# angrlline6.net
KiCad netlist of a schematic drawn in EAGLE
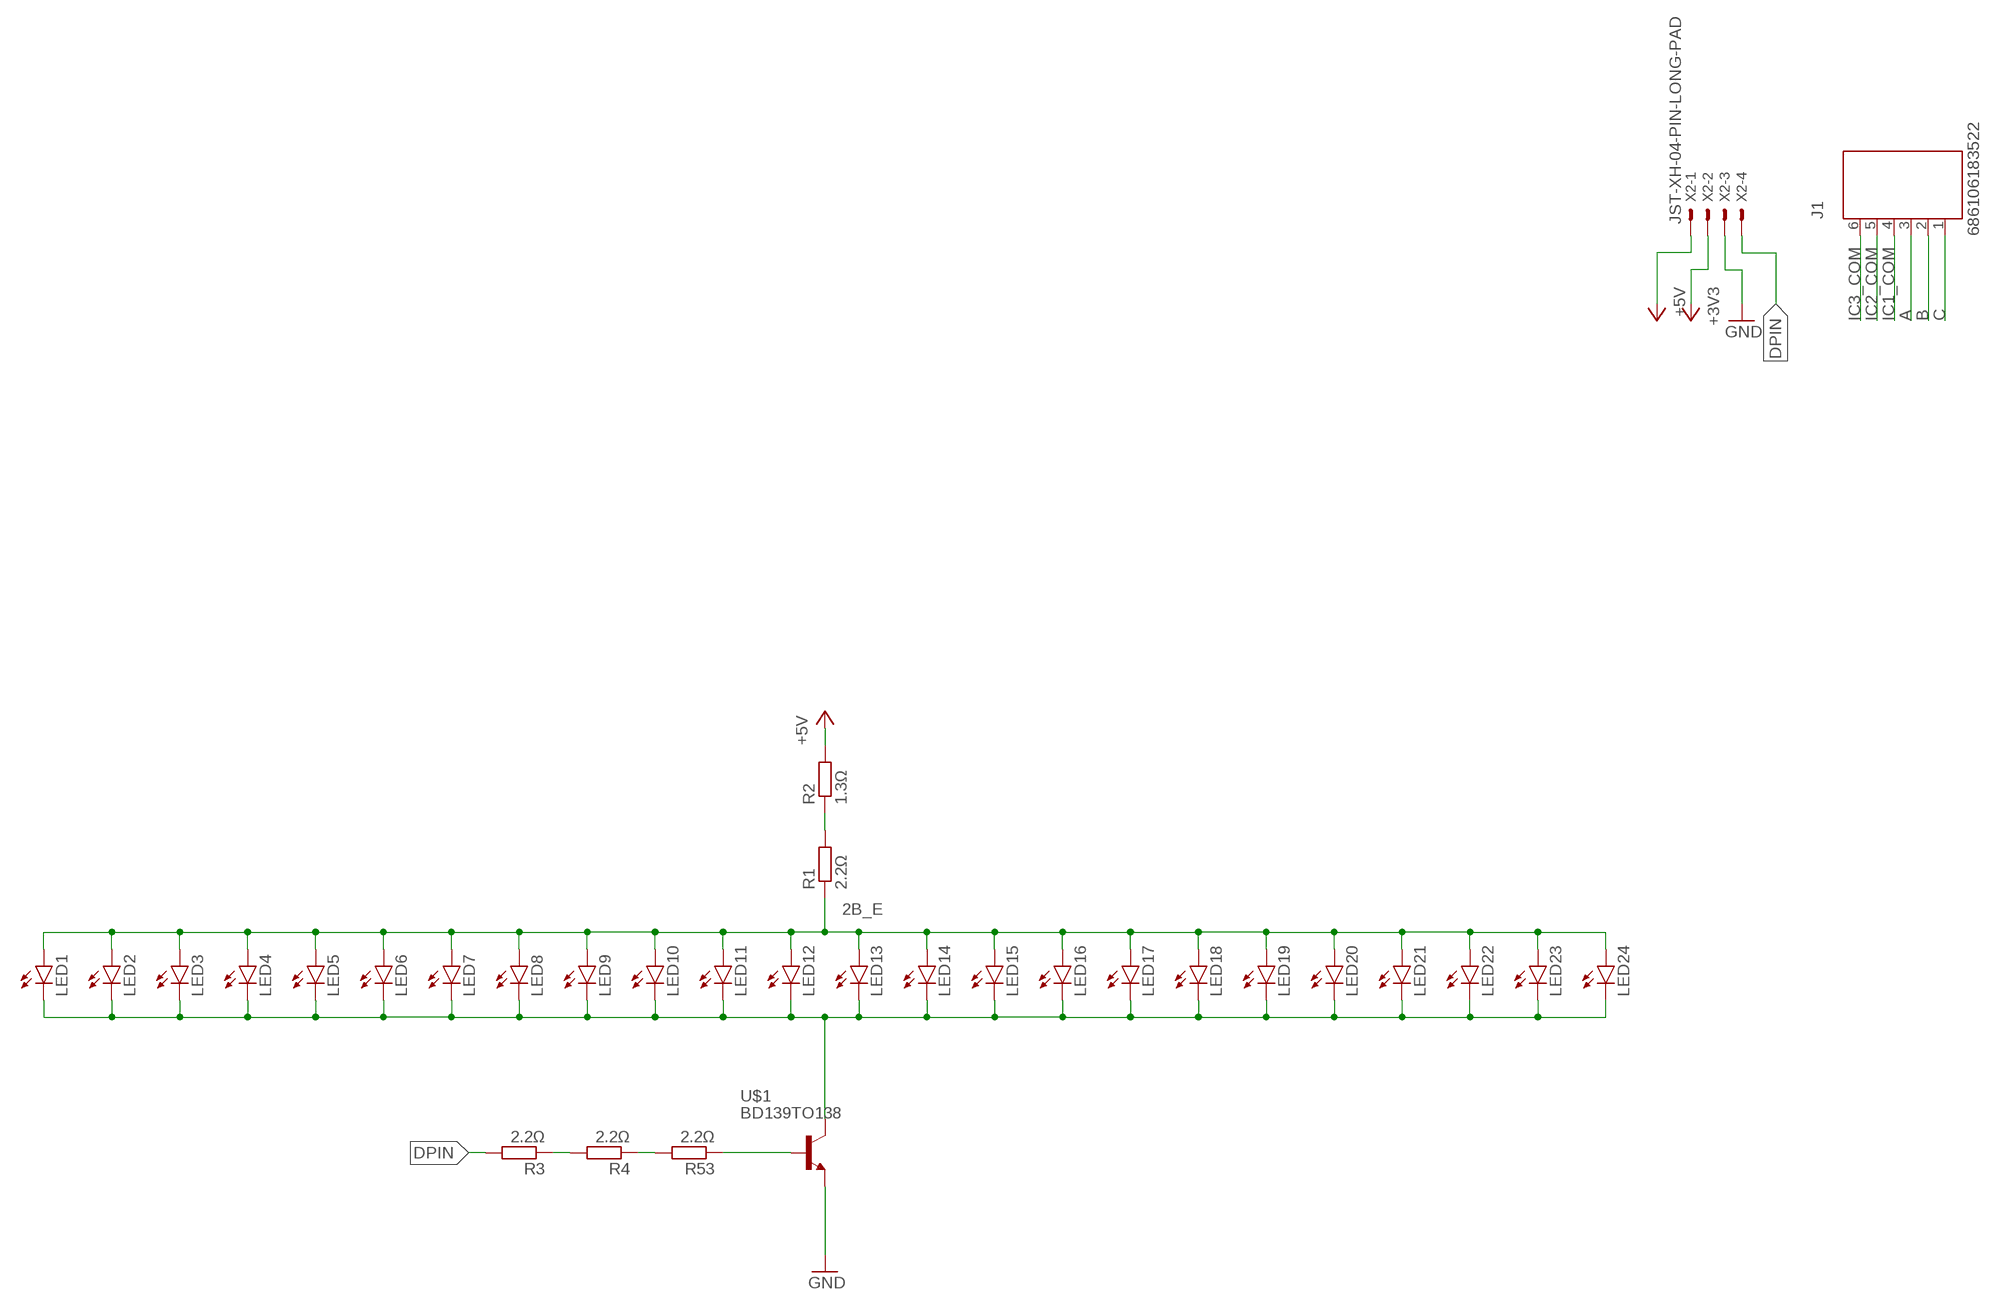
[diagram p0: schematic, sheet 1, part 1 of 2]
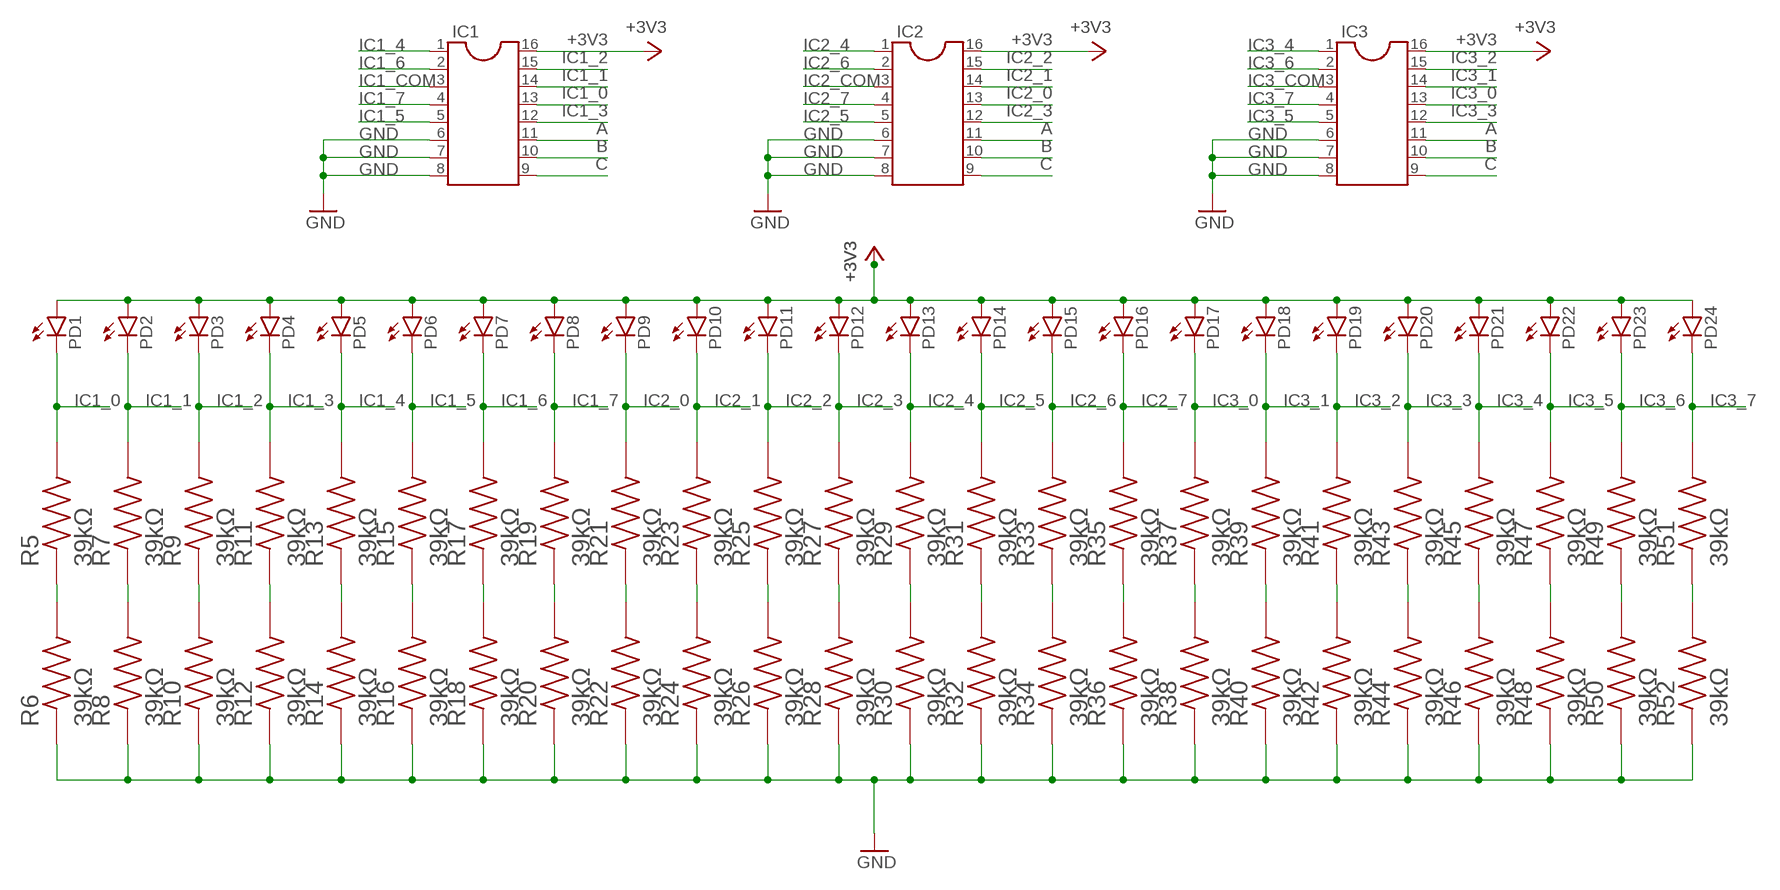
[diagram p1: schematic, sheet 1, part 2 of 2]

(export (version "E")
  (design (tool "Eeschema 10.0.6"))
  (components
    (comp (ref "IC1")
      (value "DIL16")
      (footprint "eagle-import:DIL16")
      (libsource (lib "eagle-import") (part "DIL16"))
    )
    (comp (ref "IC2")
      (value "DIL16")
      (footprint "eagle-import:DIL16")
      (libsource (lib "eagle-import") (part "DIL16"))
    )
    (comp (ref "IC3")
      (value "DIL16")
      (footprint "eagle-import:DIL16")
      (libsource (lib "eagle-import") (part "DIL16"))
    )
    (comp (ref "J1")
      (value "686106183522")
      (footprint "eagle-import:686106183522")
      (fields (field (name "MF") "Wurth Electronics"))
      (libsource (lib "eagle-import") (part "686106183522"))
    )
    (comp (ref "LED1")
      (value "LED3MM")
      (footprint "eagle-import:LED3MM")
      (libsource (lib "eagle-import") (part "LED3MM"))
    )
    (comp (ref "LED2")
      (value "LED3MM")
      (footprint "eagle-import:LED3MM")
      (libsource (lib "eagle-import") (part "LED3MM"))
    )
    (comp (ref "LED3")
      (value "LED3MM")
      (footprint "eagle-import:LED3MM")
      (libsource (lib "eagle-import") (part "LED3MM"))
    )
    (comp (ref "LED4")
      (value "LED3MM")
      (footprint "eagle-import:LED3MM")
      (libsource (lib "eagle-import") (part "LED3MM"))
    )
    (comp (ref "LED5")
      (value "LED3MM")
      (footprint "eagle-import:LED3MM")
      (libsource (lib "eagle-import") (part "LED3MM"))
    )
    (comp (ref "LED6")
      (value "LED3MM")
      (footprint "eagle-import:LED3MM")
      (libsource (lib "eagle-import") (part "LED3MM"))
    )
    (comp (ref "LED7")
      (value "LED3MM")
      (footprint "eagle-import:LED3MM")
      (libsource (lib "eagle-import") (part "LED3MM"))
    )
    (comp (ref "LED8")
      (value "LED3MM")
      (footprint "eagle-import:LED3MM")
      (libsource (lib "eagle-import") (part "LED3MM"))
    )
    (comp (ref "LED9")
      (value "LED3MM")
      (footprint "eagle-import:LED3MM")
      (libsource (lib "eagle-import") (part "LED3MM"))
    )
    (comp (ref "LED10")
      (value "LED3MM")
      (footprint "eagle-import:LED3MM")
      (libsource (lib "eagle-import") (part "LED3MM"))
    )
    (comp (ref "LED11")
      (value "LED3MM")
      (footprint "eagle-import:LED3MM")
      (libsource (lib "eagle-import") (part "LED3MM"))
    )
    (comp (ref "LED12")
      (value "LED3MM")
      (footprint "eagle-import:LED3MM")
      (libsource (lib "eagle-import") (part "LED3MM"))
    )
    (comp (ref "LED13")
      (value "LED3MM")
      (footprint "eagle-import:LED3MM")
      (libsource (lib "eagle-import") (part "LED3MM"))
    )
    (comp (ref "LED14")
      (value "LED3MM")
      (footprint "eagle-import:LED3MM")
      (libsource (lib "eagle-import") (part "LED3MM"))
    )
    (comp (ref "LED15")
      (value "LED3MM")
      (footprint "eagle-import:LED3MM")
      (libsource (lib "eagle-import") (part "LED3MM"))
    )
    (comp (ref "LED16")
      (value "LED3MM")
      (footprint "eagle-import:LED3MM")
      (libsource (lib "eagle-import") (part "LED3MM"))
    )
    (comp (ref "LED17")
      (value "LED3MM")
      (footprint "eagle-import:LED3MM")
      (libsource (lib "eagle-import") (part "LED3MM"))
    )
    (comp (ref "LED18")
      (value "LED3MM")
      (footprint "eagle-import:LED3MM")
      (libsource (lib "eagle-import") (part "LED3MM"))
    )
    (comp (ref "LED19")
      (value "LED3MM")
      (footprint "eagle-import:LED3MM")
      (libsource (lib "eagle-import") (part "LED3MM"))
    )
    (comp (ref "LED20")
      (value "LED3MM")
      (footprint "eagle-import:LED3MM")
      (libsource (lib "eagle-import") (part "LED3MM"))
    )
    (comp (ref "LED21")
      (value "LED3MM")
      (footprint "eagle-import:LED3MM")
      (libsource (lib "eagle-import") (part "LED3MM"))
    )
    (comp (ref "LED22")
      (value "LED3MM")
      (footprint "eagle-import:LED3MM")
      (libsource (lib "eagle-import") (part "LED3MM"))
    )
    (comp (ref "LED23")
      (value "LED3MM")
      (footprint "eagle-import:LED3MM")
      (libsource (lib "eagle-import") (part "LED3MM"))
    )
    (comp (ref "LED24")
      (value "LED3MM")
      (footprint "eagle-import:LED3MM")
      (libsource (lib "eagle-import") (part "LED3MM"))
    )
    (comp (ref "PD1")
      (value "LED3MM")
      (footprint "eagle-import:LED3MM")
      (libsource (lib "eagle-import") (part "LED3MM"))
    )
    (comp (ref "PD2")
      (value "LED3MM")
      (footprint "eagle-import:LED3MM")
      (libsource (lib "eagle-import") (part "LED3MM"))
    )
    (comp (ref "PD3")
      (value "LED3MM")
      (footprint "eagle-import:LED3MM")
      (libsource (lib "eagle-import") (part "LED3MM"))
    )
    (comp (ref "PD4")
      (value "LED3MM")
      (footprint "eagle-import:LED3MM")
      (libsource (lib "eagle-import") (part "LED3MM"))
    )
    (comp (ref "PD5")
      (value "LED3MM")
      (footprint "eagle-import:LED3MM")
      (libsource (lib "eagle-import") (part "LED3MM"))
    )
    (comp (ref "PD6")
      (value "LED3MM")
      (footprint "eagle-import:LED3MM")
      (libsource (lib "eagle-import") (part "LED3MM"))
    )
    (comp (ref "PD7")
      (value "LED3MM")
      (footprint "eagle-import:LED3MM")
      (libsource (lib "eagle-import") (part "LED3MM"))
    )
    (comp (ref "PD8")
      (value "LED3MM")
      (footprint "eagle-import:LED3MM")
      (libsource (lib "eagle-import") (part "LED3MM"))
    )
    (comp (ref "PD9")
      (value "LED3MM")
      (footprint "eagle-import:LED3MM")
      (libsource (lib "eagle-import") (part "LED3MM"))
    )
    (comp (ref "PD10")
      (value "LED3MM")
      (footprint "eagle-import:LED3MM")
      (libsource (lib "eagle-import") (part "LED3MM"))
    )
    (comp (ref "PD11")
      (value "LED3MM")
      (footprint "eagle-import:LED3MM")
      (libsource (lib "eagle-import") (part "LED3MM"))
    )
    (comp (ref "PD12")
      (value "LED3MM")
      (footprint "eagle-import:LED3MM")
      (libsource (lib "eagle-import") (part "LED3MM"))
    )
    (comp (ref "PD13")
      (value "LED3MM")
      (footprint "eagle-import:LED3MM")
      (libsource (lib "eagle-import") (part "LED3MM"))
    )
    (comp (ref "PD14")
      (value "LED3MM")
      (footprint "eagle-import:LED3MM")
      (libsource (lib "eagle-import") (part "LED3MM"))
    )
    (comp (ref "PD15")
      (value "LED3MM")
      (footprint "eagle-import:LED3MM")
      (libsource (lib "eagle-import") (part "LED3MM"))
    )
    (comp (ref "PD16")
      (value "LED3MM")
      (footprint "eagle-import:LED3MM")
      (libsource (lib "eagle-import") (part "LED3MM"))
    )
    (comp (ref "PD17")
      (value "LED3MM")
      (footprint "eagle-import:LED3MM")
      (libsource (lib "eagle-import") (part "LED3MM"))
    )
    (comp (ref "PD18")
      (value "LED3MM")
      (footprint "eagle-import:LED3MM")
      (libsource (lib "eagle-import") (part "LED3MM"))
    )
    (comp (ref "PD19")
      (value "LED3MM")
      (footprint "eagle-import:LED3MM")
      (libsource (lib "eagle-import") (part "LED3MM"))
    )
    (comp (ref "PD20")
      (value "LED3MM")
      (footprint "eagle-import:LED3MM")
      (libsource (lib "eagle-import") (part "LED3MM"))
    )
    (comp (ref "PD21")
      (value "LED3MM")
      (footprint "eagle-import:LED3MM")
      (libsource (lib "eagle-import") (part "LED3MM"))
    )
    (comp (ref "PD22")
      (value "LED3MM")
      (footprint "eagle-import:LED3MM")
      (libsource (lib "eagle-import") (part "LED3MM"))
    )
    (comp (ref "PD23")
      (value "LED3MM")
      (footprint "eagle-import:LED3MM")
      (libsource (lib "eagle-import") (part "LED3MM"))
    )
    (comp (ref "PD24")
      (value "LED3MM")
      (footprint "eagle-import:LED3MM")
      (libsource (lib "eagle-import") (part "LED3MM"))
    )
    (comp (ref "R1")
      (value "2.2Ω")
      (footprint "eagle-import:0207_10")
      (libsource (lib "eagle-import") (part "R-EU_0207/10"))
    )
    (comp (ref "R2")
      (value "1.3Ω")
      (footprint "eagle-import:0207_10")
      (libsource (lib "eagle-import") (part "R-EU_0207/10"))
    )
    (comp (ref "R3")
      (value "2.2Ω")
      (footprint "eagle-import:0207_10")
      (libsource (lib "eagle-import") (part "R-EU_0207/10"))
    )
    (comp (ref "R4")
      (value "2.2Ω")
      (footprint "eagle-import:0207_10")
      (libsource (lib "eagle-import") (part "R-EU_0207/10"))
    )
    (comp (ref "R5")
      (value "39kΩ")
      (footprint "eagle-import:RESC1608X55N")
      (fields
        (field (name "COMMENT") "1623094-1")
        (field (name "MF") "TE Connectivity")
        (field (name "MP") "CRG0603ZR")
      )
      (libsource (lib "eagle-import") (part "CRG0603ZR"))
    )
    (comp (ref "R6")
      (value "39kΩ")
      (footprint "eagle-import:RESC1608X55N")
      (fields
        (field (name "COMMENT") "1623094-1")
        (field (name "MF") "TE Connectivity")
        (field (name "MP") "CRG0603ZR")
      )
      (libsource (lib "eagle-import") (part "CRG0603ZR"))
    )
    (comp (ref "R7")
      (value "39kΩ")
      (footprint "eagle-import:RESC1608X55N")
      (fields
        (field (name "COMMENT") "1623094-1")
        (field (name "MF") "TE Connectivity")
        (field (name "MP") "CRG0603ZR")
      )
      (libsource (lib "eagle-import") (part "CRG0603ZR"))
    )
    (comp (ref "R8")
      (value "39kΩ")
      (footprint "eagle-import:RESC1608X55N")
      (fields
        (field (name "COMMENT") "1623094-1")
        (field (name "MF") "TE Connectivity")
        (field (name "MP") "CRG0603ZR")
      )
      (libsource (lib "eagle-import") (part "CRG0603ZR"))
    )
    (comp (ref "R9")
      (value "39kΩ")
      (footprint "eagle-import:RESC1608X55N")
      (fields
        (field (name "COMMENT") "1623094-1")
        (field (name "MF") "TE Connectivity")
        (field (name "MP") "CRG0603ZR")
      )
      (libsource (lib "eagle-import") (part "CRG0603ZR"))
    )
    (comp (ref "R10")
      (value "39kΩ")
      (footprint "eagle-import:RESC1608X55N")
      (fields
        (field (name "COMMENT") "1623094-1")
        (field (name "MF") "TE Connectivity")
        (field (name "MP") "CRG0603ZR")
      )
      (libsource (lib "eagle-import") (part "CRG0603ZR"))
    )
    (comp (ref "R11")
      (value "39kΩ")
      (footprint "eagle-import:RESC1608X55N")
      (fields
        (field (name "COMMENT") "1623094-1")
        (field (name "MF") "TE Connectivity")
        (field (name "MP") "CRG0603ZR")
      )
      (libsource (lib "eagle-import") (part "CRG0603ZR"))
    )
    (comp (ref "R12")
      (value "39kΩ")
      (footprint "eagle-import:RESC1608X55N")
      (fields
        (field (name "COMMENT") "1623094-1")
        (field (name "MF") "TE Connectivity")
        (field (name "MP") "CRG0603ZR")
      )
      (libsource (lib "eagle-import") (part "CRG0603ZR"))
    )
    (comp (ref "R13")
      (value "39kΩ")
      (footprint "eagle-import:RESC1608X55N")
      (fields
        (field (name "COMMENT") "1623094-1")
        (field (name "MF") "TE Connectivity")
        (field (name "MP") "CRG0603ZR")
      )
      (libsource (lib "eagle-import") (part "CRG0603ZR"))
    )
    (comp (ref "R14")
      (value "39kΩ")
      (footprint "eagle-import:RESC1608X55N")
      (fields
        (field (name "COMMENT") "1623094-1")
        (field (name "MF") "TE Connectivity")
        (field (name "MP") "CRG0603ZR")
      )
      (libsource (lib "eagle-import") (part "CRG0603ZR"))
    )
    (comp (ref "R15")
      (value "39kΩ")
      (footprint "eagle-import:RESC1608X55N")
      (fields
        (field (name "COMMENT") "1623094-1")
        (field (name "MF") "TE Connectivity")
        (field (name "MP") "CRG0603ZR")
      )
      (libsource (lib "eagle-import") (part "CRG0603ZR"))
    )
    (comp (ref "R16")
      (value "39kΩ")
      (footprint "eagle-import:RESC1608X55N")
      (fields
        (field (name "COMMENT") "1623094-1")
        (field (name "MF") "TE Connectivity")
        (field (name "MP") "CRG0603ZR")
      )
      (libsource (lib "eagle-import") (part "CRG0603ZR"))
    )
    (comp (ref "R17")
      (value "39kΩ")
      (footprint "eagle-import:RESC1608X55N")
      (fields
        (field (name "COMMENT") "1623094-1")
        (field (name "MF") "TE Connectivity")
        (field (name "MP") "CRG0603ZR")
      )
      (libsource (lib "eagle-import") (part "CRG0603ZR"))
    )
    (comp (ref "R18")
      (value "39kΩ")
      (footprint "eagle-import:RESC1608X55N")
      (fields
        (field (name "COMMENT") "1623094-1")
        (field (name "MF") "TE Connectivity")
        (field (name "MP") "CRG0603ZR")
      )
      (libsource (lib "eagle-import") (part "CRG0603ZR"))
    )
    (comp (ref "R19")
      (value "39kΩ")
      (footprint "eagle-import:RESC1608X55N")
      (fields
        (field (name "COMMENT") "1623094-1")
        (field (name "MF") "TE Connectivity")
        (field (name "MP") "CRG0603ZR")
      )
      (libsource (lib "eagle-import") (part "CRG0603ZR"))
    )
    (comp (ref "R20")
      (value "39kΩ")
      (footprint "eagle-import:RESC1608X55N")
      (fields
        (field (name "COMMENT") "1623094-1")
        (field (name "MF") "TE Connectivity")
        (field (name "MP") "CRG0603ZR")
      )
      (libsource (lib "eagle-import") (part "CRG0603ZR"))
    )
    (comp (ref "R21")
      (value "39kΩ")
      (footprint "eagle-import:RESC1608X55N")
      (fields
        (field (name "COMMENT") "1623094-1")
        (field (name "MF") "TE Connectivity")
        (field (name "MP") "CRG0603ZR")
      )
      (libsource (lib "eagle-import") (part "CRG0603ZR"))
    )
    (comp (ref "R22")
      (value "39kΩ")
      (footprint "eagle-import:RESC1608X55N")
      (fields
        (field (name "COMMENT") "1623094-1")
        (field (name "MF") "TE Connectivity")
        (field (name "MP") "CRG0603ZR")
      )
      (libsource (lib "eagle-import") (part "CRG0603ZR"))
    )
    (comp (ref "R23")
      (value "39kΩ")
      (footprint "eagle-import:RESC1608X55N")
      (fields
        (field (name "COMMENT") "1623094-1")
        (field (name "MF") "TE Connectivity")
        (field (name "MP") "CRG0603ZR")
      )
      (libsource (lib "eagle-import") (part "CRG0603ZR"))
    )
    (comp (ref "R24")
      (value "39kΩ")
      (footprint "eagle-import:RESC1608X55N")
      (fields
        (field (name "COMMENT") "1623094-1")
        (field (name "MF") "TE Connectivity")
        (field (name "MP") "CRG0603ZR")
      )
      (libsource (lib "eagle-import") (part "CRG0603ZR"))
    )
    (comp (ref "R25")
      (value "39kΩ")
      (footprint "eagle-import:RESC1608X55N")
      (fields
        (field (name "COMMENT") "1623094-1")
        (field (name "MF") "TE Connectivity")
        (field (name "MP") "CRG0603ZR")
      )
      (libsource (lib "eagle-import") (part "CRG0603ZR"))
    )
    (comp (ref "R26")
      (value "39kΩ")
      (footprint "eagle-import:RESC1608X55N")
      (fields
        (field (name "COMMENT") "1623094-1")
        (field (name "MF") "TE Connectivity")
        (field (name "MP") "CRG0603ZR")
      )
      (libsource (lib "eagle-import") (part "CRG0603ZR"))
    )
    (comp (ref "R27")
      (value "39kΩ")
      (footprint "eagle-import:RESC1608X55N")
      (fields
        (field (name "COMMENT") "1623094-1")
        (field (name "MF") "TE Connectivity")
        (field (name "MP") "CRG0603ZR")
      )
      (libsource (lib "eagle-import") (part "CRG0603ZR"))
    )
    (comp (ref "R28")
      (value "39kΩ")
      (footprint "eagle-import:RESC1608X55N")
      (fields
        (field (name "COMMENT") "1623094-1")
        (field (name "MF") "TE Connectivity")
        (field (name "MP") "CRG0603ZR")
      )
      (libsource (lib "eagle-import") (part "CRG0603ZR"))
    )
    (comp (ref "R29")
      (value "39kΩ")
      (footprint "eagle-import:RESC1608X55N")
      (fields
        (field (name "COMMENT") "1623094-1")
        (field (name "MF") "TE Connectivity")
        (field (name "MP") "CRG0603ZR")
      )
      (libsource (lib "eagle-import") (part "CRG0603ZR"))
    )
    (comp (ref "R30")
      (value "39kΩ")
      (footprint "eagle-import:RESC1608X55N")
      (fields
        (field (name "COMMENT") "1623094-1")
        (field (name "MF") "TE Connectivity")
        (field (name "MP") "CRG0603ZR")
      )
      (libsource (lib "eagle-import") (part "CRG0603ZR"))
    )
    (comp (ref "R31")
      (value "39kΩ")
      (footprint "eagle-import:RESC1608X55N")
      (fields
        (field (name "COMMENT") "1623094-1")
        (field (name "MF") "TE Connectivity")
        (field (name "MP") "CRG0603ZR")
      )
      (libsource (lib "eagle-import") (part "CRG0603ZR"))
    )
    (comp (ref "R32")
      (value "39kΩ")
      (footprint "eagle-import:RESC1608X55N")
      (fields
        (field (name "COMMENT") "1623094-1")
        (field (name "MF") "TE Connectivity")
        (field (name "MP") "CRG0603ZR")
      )
      (libsource (lib "eagle-import") (part "CRG0603ZR"))
    )
    (comp (ref "R33")
      (value "39kΩ")
      (footprint "eagle-import:RESC1608X55N")
      (fields
        (field (name "COMMENT") "1623094-1")
        (field (name "MF") "TE Connectivity")
        (field (name "MP") "CRG0603ZR")
      )
      (libsource (lib "eagle-import") (part "CRG0603ZR"))
    )
    (comp (ref "R34")
      (value "39kΩ")
      (footprint "eagle-import:RESC1608X55N")
      (fields
        (field (name "COMMENT") "1623094-1")
        (field (name "MF") "TE Connectivity")
        (field (name "MP") "CRG0603ZR")
      )
      (libsource (lib "eagle-import") (part "CRG0603ZR"))
    )
    (comp (ref "R35")
      (value "39kΩ")
      (footprint "eagle-import:RESC1608X55N")
      (fields
        (field (name "COMMENT") "1623094-1")
        (field (name "MF") "TE Connectivity")
        (field (name "MP") "CRG0603ZR")
      )
      (libsource (lib "eagle-import") (part "CRG0603ZR"))
    )
    (comp (ref "R36")
      (value "39kΩ")
      (footprint "eagle-import:RESC1608X55N")
      (fields
        (field (name "COMMENT") "1623094-1")
        (field (name "MF") "TE Connectivity")
        (field (name "MP") "CRG0603ZR")
      )
      (libsource (lib "eagle-import") (part "CRG0603ZR"))
    )
    (comp (ref "R37")
      (value "39kΩ")
      (footprint "eagle-import:RESC1608X55N")
      (fields
        (field (name "COMMENT") "1623094-1")
        (field (name "MF") "TE Connectivity")
        (field (name "MP") "CRG0603ZR")
      )
      (libsource (lib "eagle-import") (part "CRG0603ZR"))
    )
    (comp (ref "R38")
      (value "39kΩ")
      (footprint "eagle-import:RESC1608X55N")
      (fields
        (field (name "COMMENT") "1623094-1")
        (field (name "MF") "TE Connectivity")
        (field (name "MP") "CRG0603ZR")
      )
      (libsource (lib "eagle-import") (part "CRG0603ZR"))
    )
    (comp (ref "R39")
      (value "39kΩ")
      (footprint "eagle-import:RESC1608X55N")
      (fields
        (field (name "COMMENT") "1623094-1")
        (field (name "MF") "TE Connectivity")
        (field (name "MP") "CRG0603ZR")
      )
      (libsource (lib "eagle-import") (part "CRG0603ZR"))
    )
    (comp (ref "R40")
      (value "39kΩ")
      (footprint "eagle-import:RESC1608X55N")
      (fields
        (field (name "COMMENT") "1623094-1")
        (field (name "MF") "TE Connectivity")
        (field (name "MP") "CRG0603ZR")
      )
      (libsource (lib "eagle-import") (part "CRG0603ZR"))
    )
    (comp (ref "R41")
      (value "39kΩ")
      (footprint "eagle-import:RESC1608X55N")
      (fields
        (field (name "COMMENT") "1623094-1")
        (field (name "MF") "TE Connectivity")
        (field (name "MP") "CRG0603ZR")
      )
      (libsource (lib "eagle-import") (part "CRG0603ZR"))
    )
    (comp (ref "R42")
      (value "39kΩ")
      (footprint "eagle-import:RESC1608X55N")
      (fields
        (field (name "COMMENT") "1623094-1")
        (field (name "MF") "TE Connectivity")
        (field (name "MP") "CRG0603ZR")
      )
      (libsource (lib "eagle-import") (part "CRG0603ZR"))
    )
    (comp (ref "R43")
      (value "39kΩ")
      (footprint "eagle-import:RESC1608X55N")
      (fields
        (field (name "COMMENT") "1623094-1")
        (field (name "MF") "TE Connectivity")
        (field (name "MP") "CRG0603ZR")
      )
      (libsource (lib "eagle-import") (part "CRG0603ZR"))
    )
    (comp (ref "R44")
      (value "39kΩ")
      (footprint "eagle-import:RESC1608X55N")
      (fields
        (field (name "COMMENT") "1623094-1")
        (field (name "MF") "TE Connectivity")
        (field (name "MP") "CRG0603ZR")
      )
      (libsource (lib "eagle-import") (part "CRG0603ZR"))
    )
    (comp (ref "R45")
      (value "39kΩ")
      (footprint "eagle-import:RESC1608X55N")
      (fields
        (field (name "COMMENT") "1623094-1")
        (field (name "MF") "TE Connectivity")
        (field (name "MP") "CRG0603ZR")
      )
      (libsource (lib "eagle-import") (part "CRG0603ZR"))
    )
    (comp (ref "R46")
      (value "39kΩ")
      (footprint "eagle-import:RESC1608X55N")
      (fields
        (field (name "COMMENT") "1623094-1")
        (field (name "MF") "TE Connectivity")
        (field (name "MP") "CRG0603ZR")
      )
      (libsource (lib "eagle-import") (part "CRG0603ZR"))
    )
    (comp (ref "R47")
      (value "39kΩ")
      (footprint "eagle-import:RESC1608X55N")
      (fields
        (field (name "COMMENT") "1623094-1")
        (field (name "MF") "TE Connectivity")
        (field (name "MP") "CRG0603ZR")
      )
      (libsource (lib "eagle-import") (part "CRG0603ZR"))
    )
    (comp (ref "R48")
      (value "39kΩ")
      (footprint "eagle-import:RESC1608X55N")
      (fields
        (field (name "COMMENT") "1623094-1")
        (field (name "MF") "TE Connectivity")
        (field (name "MP") "CRG0603ZR")
      )
      (libsource (lib "eagle-import") (part "CRG0603ZR"))
    )
    (comp (ref "R49")
      (value "39kΩ")
      (footprint "eagle-import:RESC1608X55N")
      (fields
        (field (name "COMMENT") "1623094-1")
        (field (name "MF") "TE Connectivity")
        (field (name "MP") "CRG0603ZR")
      )
      (libsource (lib "eagle-import") (part "CRG0603ZR"))
    )
    (comp (ref "R50")
      (value "39kΩ")
      (footprint "eagle-import:RESC1608X55N")
      (fields
        (field (name "COMMENT") "1623094-1")
        (field (name "MF") "TE Connectivity")
        (field (name "MP") "CRG0603ZR")
      )
      (libsource (lib "eagle-import") (part "CRG0603ZR"))
    )
    (comp (ref "R51")
      (value "39kΩ")
      (footprint "eagle-import:RESC1608X55N")
      (fields
        (field (name "COMMENT") "1623094-1")
        (field (name "MF") "TE Connectivity")
        (field (name "MP") "CRG0603ZR")
      )
      (libsource (lib "eagle-import") (part "CRG0603ZR"))
    )
    (comp (ref "R52")
      (value "39kΩ")
      (footprint "eagle-import:RESC1608X55N")
      (fields
        (field (name "COMMENT") "1623094-1")
        (field (name "MF") "TE Connectivity")
        (field (name "MP") "CRG0603ZR")
      )
      (libsource (lib "eagle-import") (part "CRG0603ZR"))
    )
    (comp (ref "R53")
      (value "2.2Ω")
      (footprint "eagle-import:0207_10")
      (libsource (lib "eagle-import") (part "R-EU_0207/10"))
    )
    (comp (ref "U$1")
      (value "BD139TO138")
      (footprint "eagle-import:TO126")
      (fields (field (name "MF") "ON") (field (name "MP") "BD139"))
      (libsource (lib "eagle-import") (part "BD139TO138"))
    )
    (comp (ref "X2")
      (value "JST-XH-04-PIN-LONG-PAD")
      (footprint "eagle-import:JST-XH-04-PACKAGE-LONG-PAD")
      (libsource (lib "eagle-import") (part "JST-XH-04-PIN-LONG-PAD"))
    )
  )
  (nets
    (net (code "1") (name "+3V3") (class "Default")
      (node (ref "IC1") (pin "16") (pinfunction "16_16") (pintype "passive"))
      (node (ref "IC2") (pin "16") (pinfunction "16_16") (pintype "passive"))
      (node (ref "IC3") (pin "16") (pinfunction "16_16") (pintype "passive"))
      (node (ref "PD1") (pin "A") (pinfunction "A_A") (pintype "passive"))
      (node (ref "PD10") (pin "A") (pinfunction "A_A") (pintype "passive"))
      (node (ref "PD11") (pin "A") (pinfunction "A_A") (pintype "passive"))
      (node (ref "PD12") (pin "A") (pinfunction "A_A") (pintype "passive"))
      (node (ref "PD13") (pin "A") (pinfunction "A_A") (pintype "passive"))
      (node (ref "PD14") (pin "A") (pinfunction "A_A") (pintype "passive"))
      (node (ref "PD15") (pin "A") (pinfunction "A_A") (pintype "passive"))
      (node (ref "PD16") (pin "A") (pinfunction "A_A") (pintype "passive"))
      (node (ref "PD17") (pin "A") (pinfunction "A_A") (pintype "passive"))
      (node (ref "PD18") (pin "A") (pinfunction "A_A") (pintype "passive"))
      (node (ref "PD19") (pin "A") (pinfunction "A_A") (pintype "passive"))
      (node (ref "PD2") (pin "A") (pinfunction "A_A") (pintype "passive"))
      (node (ref "PD20") (pin "A") (pinfunction "A_A") (pintype "passive"))
      (node (ref "PD21") (pin "A") (pinfunction "A_A") (pintype "passive"))
      (node (ref "PD22") (pin "A") (pinfunction "A_A") (pintype "passive"))
      (node (ref "PD23") (pin "A") (pinfunction "A_A") (pintype "passive"))
      (node (ref "PD24") (pin "A") (pinfunction "A_A") (pintype "passive"))
      (node (ref "PD3") (pin "A") (pinfunction "A_A") (pintype "passive"))
      (node (ref "PD4") (pin "A") (pinfunction "A_A") (pintype "passive"))
      (node (ref "PD5") (pin "A") (pinfunction "A_A") (pintype "passive"))
      (node (ref "PD6") (pin "A") (pinfunction "A_A") (pintype "passive"))
      (node (ref "PD7") (pin "A") (pinfunction "A_A") (pintype "passive"))
      (node (ref "PD8") (pin "A") (pinfunction "A_A") (pintype "passive"))
      (node (ref "PD9") (pin "A") (pinfunction "A_A") (pintype "passive"))
      (node (ref "X2") (pin "2") (pinfunction "S_2") (pintype "passive"))
    )
    (net (code "2") (name "+5V") (class "Default")
      (node (ref "R2") (pin "2") (pinfunction "2_2") (pintype "passive"))
      (node (ref "X2") (pin "1") (pinfunction "S_1") (pintype "passive"))
    )
    (net (code "3") (name "/2B_E") (class "Default")
      (node (ref "LED1") (pin "A") (pinfunction "A_A") (pintype "passive"))
      (node (ref "LED10") (pin "A") (pinfunction "A_A") (pintype "passive"))
      (node (ref "LED11") (pin "A") (pinfunction "A_A") (pintype "passive"))
      (node (ref "LED12") (pin "A") (pinfunction "A_A") (pintype "passive"))
      (node (ref "LED13") (pin "A") (pinfunction "A_A") (pintype "passive"))
      (node (ref "LED14") (pin "A") (pinfunction "A_A") (pintype "passive"))
      (node (ref "LED15") (pin "A") (pinfunction "A_A") (pintype "passive"))
      (node (ref "LED16") (pin "A") (pinfunction "A_A") (pintype "passive"))
      (node (ref "LED17") (pin "A") (pinfunction "A_A") (pintype "passive"))
      (node (ref "LED18") (pin "A") (pinfunction "A_A") (pintype "passive"))
      (node (ref "LED19") (pin "A") (pinfunction "A_A") (pintype "passive"))
      (node (ref "LED2") (pin "A") (pinfunction "A_A") (pintype "passive"))
      (node (ref "LED20") (pin "A") (pinfunction "A_A") (pintype "passive"))
      (node (ref "LED21") (pin "A") (pinfunction "A_A") (pintype "passive"))
      (node (ref "LED22") (pin "A") (pinfunction "A_A") (pintype "passive"))
      (node (ref "LED23") (pin "A") (pinfunction "A_A") (pintype "passive"))
      (node (ref "LED24") (pin "A") (pinfunction "A_A") (pintype "passive"))
      (node (ref "LED3") (pin "A") (pinfunction "A_A") (pintype "passive"))
      (node (ref "LED4") (pin "A") (pinfunction "A_A") (pintype "passive"))
      (node (ref "LED5") (pin "A") (pinfunction "A_A") (pintype "passive"))
      (node (ref "LED6") (pin "A") (pinfunction "A_A") (pintype "passive"))
      (node (ref "LED7") (pin "A") (pinfunction "A_A") (pintype "passive"))
      (node (ref "LED8") (pin "A") (pinfunction "A_A") (pintype "passive"))
      (node (ref "LED9") (pin "A") (pinfunction "A_A") (pintype "passive"))
      (node (ref "R1") (pin "1") (pinfunction "1_1") (pintype "passive"))
    )
    (net (code "4") (name "/A") (class "Default")
      (node (ref "IC1") (pin "11") (pinfunction "11_11") (pintype "passive"))
      (node (ref "IC2") (pin "11") (pinfunction "11_11") (pintype "passive"))
      (node (ref "IC3") (pin "11") (pinfunction "11_11") (pintype "passive"))
      (node (ref "J1") (pin "3") (pinfunction "4_3") (pintype "passive"))
    )
    (net (code "5") (name "/B") (class "Default")
      (node (ref "IC1") (pin "10") (pinfunction "10_10") (pintype "passive"))
      (node (ref "IC2") (pin "10") (pinfunction "10_10") (pintype "passive"))
      (node (ref "IC3") (pin "10") (pinfunction "10_10") (pintype "passive"))
      (node (ref "J1") (pin "2") (pinfunction "5_2") (pintype "passive"))
    )
    (net (code "6") (name "/C") (class "Default")
      (node (ref "IC1") (pin "9") (pinfunction "9_9") (pintype "passive"))
      (node (ref "IC2") (pin "9") (pinfunction "9_9") (pintype "passive"))
      (node (ref "IC3") (pin "9") (pinfunction "9_9") (pintype "passive"))
      (node (ref "J1") (pin "1") (pinfunction "6_1") (pintype "passive"))
    )
    (net (code "7") (name "/IC1_0") (class "Default")
      (node (ref "IC1") (pin "13") (pinfunction "13_13") (pintype "passive"))
      (node (ref "PD1") (pin "K") (pinfunction "C_K") (pintype "passive"))
      (node (ref "R5") (pin "2") (pinfunction "2_2") (pintype "passive"))
    )
    (net (code "8") (name "/IC1_1") (class "Default")
      (node (ref "IC1") (pin "14") (pinfunction "14_14") (pintype "passive"))
      (node (ref "PD2") (pin "K") (pinfunction "C_K") (pintype "passive"))
      (node (ref "R7") (pin "2") (pinfunction "2_2") (pintype "passive"))
    )
    (net (code "9") (name "/IC1_2") (class "Default")
      (node (ref "IC1") (pin "15") (pinfunction "15_15") (pintype "passive"))
      (node (ref "PD3") (pin "K") (pinfunction "C_K") (pintype "passive"))
      (node (ref "R9") (pin "2") (pinfunction "2_2") (pintype "passive"))
    )
    (net (code "10") (name "/IC1_3") (class "Default")
      (node (ref "IC1") (pin "12") (pinfunction "12_12") (pintype "passive"))
      (node (ref "PD4") (pin "K") (pinfunction "C_K") (pintype "passive"))
      (node (ref "R11") (pin "2") (pinfunction "2_2") (pintype "passive"))
    )
    (net (code "11") (name "/IC1_4") (class "Default")
      (node (ref "IC1") (pin "1") (pinfunction "1_1") (pintype "passive"))
      (node (ref "PD5") (pin "K") (pinfunction "C_K") (pintype "passive"))
      (node (ref "R13") (pin "2") (pinfunction "2_2") (pintype "passive"))
    )
    (net (code "12") (name "/IC1_5") (class "Default")
      (node (ref "IC1") (pin "5") (pinfunction "5_5") (pintype "passive"))
      (node (ref "PD6") (pin "K") (pinfunction "C_K") (pintype "passive"))
      (node (ref "R15") (pin "2") (pinfunction "2_2") (pintype "passive"))
    )
    (net (code "13") (name "/IC1_6") (class "Default")
      (node (ref "IC1") (pin "2") (pinfunction "2_2") (pintype "passive"))
      (node (ref "PD7") (pin "K") (pinfunction "C_K") (pintype "passive"))
      (node (ref "R17") (pin "2") (pinfunction "2_2") (pintype "passive"))
    )
    (net (code "14") (name "/IC1_7") (class "Default")
      (node (ref "IC1") (pin "4") (pinfunction "4_4") (pintype "passive"))
      (node (ref "PD8") (pin "K") (pinfunction "C_K") (pintype "passive"))
      (node (ref "R19") (pin "2") (pinfunction "2_2") (pintype "passive"))
    )
    (net (code "15") (name "/IC1_COM") (class "Default")
      (node (ref "IC1") (pin "3") (pinfunction "3_3") (pintype "passive"))
      (node (ref "J1") (pin "4") (pinfunction "3_4") (pintype "passive"))
    )
    (net (code "16") (name "/IC2_0") (class "Default")
      (node (ref "IC2") (pin "13") (pinfunction "13_13") (pintype "passive"))
      (node (ref "PD9") (pin "K") (pinfunction "C_K") (pintype "passive"))
      (node (ref "R21") (pin "2") (pinfunction "2_2") (pintype "passive"))
    )
    (net (code "17") (name "/IC2_1") (class "Default")
      (node (ref "IC2") (pin "14") (pinfunction "14_14") (pintype "passive"))
      (node (ref "PD10") (pin "K") (pinfunction "C_K") (pintype "passive"))
      (node (ref "R23") (pin "2") (pinfunction "2_2") (pintype "passive"))
    )
    (net (code "18") (name "/IC2_2") (class "Default")
      (node (ref "IC2") (pin "15") (pinfunction "15_15") (pintype "passive"))
      (node (ref "PD11") (pin "K") (pinfunction "C_K") (pintype "passive"))
      (node (ref "R25") (pin "2") (pinfunction "2_2") (pintype "passive"))
    )
    (net (code "19") (name "/IC2_3") (class "Default")
      (node (ref "IC2") (pin "12") (pinfunction "12_12") (pintype "passive"))
      (node (ref "PD12") (pin "K") (pinfunction "C_K") (pintype "passive"))
      (node (ref "R27") (pin "2") (pinfunction "2_2") (pintype "passive"))
    )
    (net (code "20") (name "/IC2_4") (class "Default")
      (node (ref "IC2") (pin "1") (pinfunction "1_1") (pintype "passive"))
      (node (ref "PD13") (pin "K") (pinfunction "C_K") (pintype "passive"))
      (node (ref "R29") (pin "2") (pinfunction "2_2") (pintype "passive"))
    )
    (net (code "21") (name "/IC2_5") (class "Default")
      (node (ref "IC2") (pin "5") (pinfunction "5_5") (pintype "passive"))
      (node (ref "PD14") (pin "K") (pinfunction "C_K") (pintype "passive"))
      (node (ref "R31") (pin "2") (pinfunction "2_2") (pintype "passive"))
    )
    (net (code "22") (name "/IC2_6") (class "Default")
      (node (ref "IC2") (pin "2") (pinfunction "2_2") (pintype "passive"))
      (node (ref "PD15") (pin "K") (pinfunction "C_K") (pintype "passive"))
      (node (ref "R33") (pin "2") (pinfunction "2_2") (pintype "passive"))
    )
    (net (code "23") (name "/IC2_7") (class "Default")
      (node (ref "IC2") (pin "4") (pinfunction "4_4") (pintype "passive"))
      (node (ref "PD16") (pin "K") (pinfunction "C_K") (pintype "passive"))
      (node (ref "R35") (pin "2") (pinfunction "2_2") (pintype "passive"))
    )
    (net (code "24") (name "/IC2_COM") (class "Default")
      (node (ref "IC2") (pin "3") (pinfunction "3_3") (pintype "passive"))
      (node (ref "J1") (pin "5") (pinfunction "2_5") (pintype "passive"))
    )
    (net (code "25") (name "/IC3_0") (class "Default")
      (node (ref "IC3") (pin "13") (pinfunction "13_13") (pintype "passive"))
      (node (ref "PD17") (pin "K") (pinfunction "C_K") (pintype "passive"))
      (node (ref "R37") (pin "2") (pinfunction "2_2") (pintype "passive"))
    )
    (net (code "26") (name "/IC3_1") (class "Default")
      (node (ref "IC3") (pin "14") (pinfunction "14_14") (pintype "passive"))
      (node (ref "PD18") (pin "K") (pinfunction "C_K") (pintype "passive"))
      (node (ref "R39") (pin "2") (pinfunction "2_2") (pintype "passive"))
    )
    (net (code "27") (name "/IC3_2") (class "Default")
      (node (ref "IC3") (pin "15") (pinfunction "15_15") (pintype "passive"))
      (node (ref "PD19") (pin "K") (pinfunction "C_K") (pintype "passive"))
      (node (ref "R41") (pin "2") (pinfunction "2_2") (pintype "passive"))
    )
    (net (code "28") (name "/IC3_3") (class "Default")
      (node (ref "IC3") (pin "12") (pinfunction "12_12") (pintype "passive"))
      (node (ref "PD20") (pin "K") (pinfunction "C_K") (pintype "passive"))
      (node (ref "R43") (pin "2") (pinfunction "2_2") (pintype "passive"))
    )
    (net (code "29") (name "/IC3_4") (class "Default")
      (node (ref "IC3") (pin "1") (pinfunction "1_1") (pintype "passive"))
      (node (ref "PD21") (pin "K") (pinfunction "C_K") (pintype "passive"))
      (node (ref "R45") (pin "2") (pinfunction "2_2") (pintype "passive"))
    )
    (net (code "30") (name "/IC3_5") (class "Default")
      (node (ref "IC3") (pin "5") (pinfunction "5_5") (pintype "passive"))
      (node (ref "PD22") (pin "K") (pinfunction "C_K") (pintype "passive"))
      (node (ref "R47") (pin "2") (pinfunction "2_2") (pintype "passive"))
    )
    (net (code "31") (name "/IC3_6") (class "Default")
      (node (ref "IC3") (pin "2") (pinfunction "2_2") (pintype "passive"))
      (node (ref "PD23") (pin "K") (pinfunction "C_K") (pintype "passive"))
      (node (ref "R49") (pin "2") (pinfunction "2_2") (pintype "passive"))
    )
    (net (code "32") (name "/IC3_7") (class "Default")
      (node (ref "IC3") (pin "4") (pinfunction "4_4") (pintype "passive"))
      (node (ref "PD24") (pin "K") (pinfunction "C_K") (pintype "passive"))
      (node (ref "R51") (pin "2") (pinfunction "2_2") (pintype "passive"))
    )
    (net (code "33") (name "/IC3_COM") (class "Default")
      (node (ref "IC3") (pin "3") (pinfunction "3_3") (pintype "passive"))
      (node (ref "J1") (pin "6") (pinfunction "1_6") (pintype "passive"))
    )
    (net (code "34") (name "DPIN") (class "Default")
      (node (ref "R3") (pin "2") (pinfunction "2_2") (pintype "passive"))
      (node (ref "X2") (pin "4") (pinfunction "S_4") (pintype "passive"))
    )
    (net (code "35") (name "GND") (class "Default")
      (node (ref "IC1") (pin "6") (pinfunction "6_6") (pintype "passive"))
      (node (ref "IC1") (pin "7") (pinfunction "7_7") (pintype "passive"))
      (node (ref "IC1") (pin "8") (pinfunction "8_8") (pintype "passive"))
      (node (ref "IC2") (pin "6") (pinfunction "6_6") (pintype "passive"))
      (node (ref "IC2") (pin "7") (pinfunction "7_7") (pintype "passive"))
      (node (ref "IC2") (pin "8") (pinfunction "8_8") (pintype "passive"))
      (node (ref "IC3") (pin "6") (pinfunction "6_6") (pintype "passive"))
      (node (ref "IC3") (pin "7") (pinfunction "7_7") (pintype "passive"))
      (node (ref "IC3") (pin "8") (pinfunction "8_8") (pintype "passive"))
      (node (ref "R10") (pin "1") (pinfunction "1_1") (pintype "passive"))
      (node (ref "R12") (pin "1") (pinfunction "1_1") (pintype "passive"))
      (node (ref "R14") (pin "1") (pinfunction "1_1") (pintype "passive"))
      (node (ref "R16") (pin "1") (pinfunction "1_1") (pintype "passive"))
      (node (ref "R18") (pin "1") (pinfunction "1_1") (pintype "passive"))
      (node (ref "R20") (pin "1") (pinfunction "1_1") (pintype "passive"))
      (node (ref "R22") (pin "1") (pinfunction "1_1") (pintype "passive"))
      (node (ref "R24") (pin "1") (pinfunction "1_1") (pintype "passive"))
      (node (ref "R26") (pin "1") (pinfunction "1_1") (pintype "passive"))
      (node (ref "R28") (pin "1") (pinfunction "1_1") (pintype "passive"))
      (node (ref "R30") (pin "1") (pinfunction "1_1") (pintype "passive"))
      (node (ref "R32") (pin "1") (pinfunction "1_1") (pintype "passive"))
      (node (ref "R34") (pin "1") (pinfunction "1_1") (pintype "passive"))
      (node (ref "R36") (pin "1") (pinfunction "1_1") (pintype "passive"))
      (node (ref "R38") (pin "1") (pinfunction "1_1") (pintype "passive"))
      (node (ref "R40") (pin "1") (pinfunction "1_1") (pintype "passive"))
      (node (ref "R42") (pin "1") (pinfunction "1_1") (pintype "passive"))
      (node (ref "R44") (pin "1") (pinfunction "1_1") (pintype "passive"))
      (node (ref "R46") (pin "1") (pinfunction "1_1") (pintype "passive"))
      (node (ref "R48") (pin "1") (pinfunction "1_1") (pintype "passive"))
      (node (ref "R50") (pin "1") (pinfunction "1_1") (pintype "passive"))
      (node (ref "R52") (pin "1") (pinfunction "1_1") (pintype "passive"))
      (node (ref "R6") (pin "1") (pinfunction "1_1") (pintype "passive"))
      (node (ref "R8") (pin "1") (pinfunction "1_1") (pintype "passive"))
      (node (ref "U$1") (pin "E") (pinfunction "E_E") (pintype "passive"))
      (node (ref "X2") (pin "3") (pinfunction "S_3") (pintype "passive"))
    )
    (net (code "36") (name "Net-(LED1-C)") (class "Default")
      (node (ref "LED1") (pin "K") (pinfunction "C_K") (pintype "passive"))
      (node (ref "LED10") (pin "K") (pinfunction "C_K") (pintype "passive"))
      (node (ref "LED11") (pin "K") (pinfunction "C_K") (pintype "passive"))
      (node (ref "LED12") (pin "K") (pinfunction "C_K") (pintype "passive"))
      (node (ref "LED13") (pin "K") (pinfunction "C_K") (pintype "passive"))
      (node (ref "LED14") (pin "K") (pinfunction "C_K") (pintype "passive"))
      (node (ref "LED15") (pin "K") (pinfunction "C_K") (pintype "passive"))
      (node (ref "LED16") (pin "K") (pinfunction "C_K") (pintype "passive"))
      (node (ref "LED17") (pin "K") (pinfunction "C_K") (pintype "passive"))
      (node (ref "LED18") (pin "K") (pinfunction "C_K") (pintype "passive"))
      (node (ref "LED19") (pin "K") (pinfunction "C_K") (pintype "passive"))
      (node (ref "LED2") (pin "K") (pinfunction "C_K") (pintype "passive"))
      (node (ref "LED20") (pin "K") (pinfunction "C_K") (pintype "passive"))
      (node (ref "LED21") (pin "K") (pinfunction "C_K") (pintype "passive"))
      (node (ref "LED22") (pin "K") (pinfunction "C_K") (pintype "passive"))
      (node (ref "LED23") (pin "K") (pinfunction "C_K") (pintype "passive"))
      (node (ref "LED24") (pin "K") (pinfunction "C_K") (pintype "passive"))
      (node (ref "LED3") (pin "K") (pinfunction "C_K") (pintype "passive"))
      (node (ref "LED4") (pin "K") (pinfunction "C_K") (pintype "passive"))
      (node (ref "LED5") (pin "K") (pinfunction "C_K") (pintype "passive"))
      (node (ref "LED6") (pin "K") (pinfunction "C_K") (pintype "passive"))
      (node (ref "LED7") (pin "K") (pinfunction "C_K") (pintype "passive"))
      (node (ref "LED8") (pin "K") (pinfunction "C_K") (pintype "passive"))
      (node (ref "LED9") (pin "K") (pinfunction "C_K") (pintype "passive"))
      (node (ref "U$1") (pin "C") (pinfunction "C_C") (pintype "passive"))
    )
    (net (code "37") (name "Net-(R1-Pad2)") (class "Default")
      (node (ref "R1") (pin "2") (pinfunction "2_2") (pintype "passive"))
      (node (ref "R2") (pin "1") (pinfunction "1_1") (pintype "passive"))
    )
    (net (code "38") (name "Net-(R3-Pad1)") (class "Default")
      (node (ref "R3") (pin "1") (pinfunction "1_1") (pintype "passive"))
      (node (ref "R4") (pin "2") (pinfunction "2_2") (pintype "passive"))
    )
    (net (code "39") (name "Net-(R4-Pad1)") (class "Default")
      (node (ref "R4") (pin "1") (pinfunction "1_1") (pintype "passive"))
      (node (ref "R53") (pin "2") (pinfunction "2_2") (pintype "passive"))
    )
    (net (code "40") (name "Net-(R5-Pad1)") (class "Default")
      (node (ref "R5") (pin "1") (pinfunction "1_1") (pintype "passive"))
      (node (ref "R6") (pin "2") (pinfunction "2_2") (pintype "passive"))
    )
    (net (code "41") (name "Net-(R7-Pad1)") (class "Default")
      (node (ref "R7") (pin "1") (pinfunction "1_1") (pintype "passive"))
      (node (ref "R8") (pin "2") (pinfunction "2_2") (pintype "passive"))
    )
    (net (code "42") (name "Net-(R10-Pad2)") (class "Default")
      (node (ref "R10") (pin "2") (pinfunction "2_2") (pintype "passive"))
      (node (ref "R9") (pin "1") (pinfunction "1_1") (pintype "passive"))
    )
    (net (code "43") (name "Net-(R11-Pad1)") (class "Default")
      (node (ref "R11") (pin "1") (pinfunction "1_1") (pintype "passive"))
      (node (ref "R12") (pin "2") (pinfunction "2_2") (pintype "passive"))
    )
    (net (code "44") (name "Net-(R13-Pad1)") (class "Default")
      (node (ref "R13") (pin "1") (pinfunction "1_1") (pintype "passive"))
      (node (ref "R14") (pin "2") (pinfunction "2_2") (pintype "passive"))
    )
    (net (code "45") (name "Net-(R15-Pad1)") (class "Default")
      (node (ref "R15") (pin "1") (pinfunction "1_1") (pintype "passive"))
      (node (ref "R16") (pin "2") (pinfunction "2_2") (pintype "passive"))
    )
    (net (code "46") (name "Net-(R17-Pad1)") (class "Default")
      (node (ref "R17") (pin "1") (pinfunction "1_1") (pintype "passive"))
      (node (ref "R18") (pin "2") (pinfunction "2_2") (pintype "passive"))
    )
    (net (code "47") (name "Net-(R19-Pad1)") (class "Default")
      (node (ref "R19") (pin "1") (pinfunction "1_1") (pintype "passive"))
      (node (ref "R20") (pin "2") (pinfunction "2_2") (pintype "passive"))
    )
    (net (code "48") (name "Net-(R21-Pad1)") (class "Default")
      (node (ref "R21") (pin "1") (pinfunction "1_1") (pintype "passive"))
      (node (ref "R22") (pin "2") (pinfunction "2_2") (pintype "passive"))
    )
    (net (code "49") (name "Net-(R23-Pad1)") (class "Default")
      (node (ref "R23") (pin "1") (pinfunction "1_1") (pintype "passive"))
      (node (ref "R24") (pin "2") (pinfunction "2_2") (pintype "passive"))
    )
    (net (code "50") (name "Net-(R25-Pad1)") (class "Default")
      (node (ref "R25") (pin "1") (pinfunction "1_1") (pintype "passive"))
      (node (ref "R26") (pin "2") (pinfunction "2_2") (pintype "passive"))
    )
    (net (code "51") (name "Net-(R27-Pad1)") (class "Default")
      (node (ref "R27") (pin "1") (pinfunction "1_1") (pintype "passive"))
      (node (ref "R28") (pin "2") (pinfunction "2_2") (pintype "passive"))
    )
    (net (code "52") (name "Net-(R29-Pad1)") (class "Default")
      (node (ref "R29") (pin "1") (pinfunction "1_1") (pintype "passive"))
      (node (ref "R30") (pin "2") (pinfunction "2_2") (pintype "passive"))
    )
    (net (code "53") (name "Net-(R31-Pad1)") (class "Default")
      (node (ref "R31") (pin "1") (pinfunction "1_1") (pintype "passive"))
      (node (ref "R32") (pin "2") (pinfunction "2_2") (pintype "passive"))
    )
    (net (code "54") (name "Net-(R33-Pad1)") (class "Default")
      (node (ref "R33") (pin "1") (pinfunction "1_1") (pintype "passive"))
      (node (ref "R34") (pin "2") (pinfunction "2_2") (pintype "passive"))
    )
    (net (code "55") (name "Net-(R35-Pad1)") (class "Default")
      (node (ref "R35") (pin "1") (pinfunction "1_1") (pintype "passive"))
      (node (ref "R36") (pin "2") (pinfunction "2_2") (pintype "passive"))
    )
    (net (code "56") (name "Net-(R37-Pad1)") (class "Default")
      (node (ref "R37") (pin "1") (pinfunction "1_1") (pintype "passive"))
      (node (ref "R38") (pin "2") (pinfunction "2_2") (pintype "passive"))
    )
    (net (code "57") (name "Net-(R39-Pad1)") (class "Default")
      (node (ref "R39") (pin "1") (pinfunction "1_1") (pintype "passive"))
      (node (ref "R40") (pin "2") (pinfunction "2_2") (pintype "passive"))
    )
    (net (code "58") (name "Net-(R41-Pad1)") (class "Default")
      (node (ref "R41") (pin "1") (pinfunction "1_1") (pintype "passive"))
      (node (ref "R42") (pin "2") (pinfunction "2_2") (pintype "passive"))
    )
    (net (code "59") (name "Net-(R43-Pad1)") (class "Default")
      (node (ref "R43") (pin "1") (pinfunction "1_1") (pintype "passive"))
      (node (ref "R44") (pin "2") (pinfunction "2_2") (pintype "passive"))
    )
    (net (code "60") (name "Net-(R45-Pad1)") (class "Default")
      (node (ref "R45") (pin "1") (pinfunction "1_1") (pintype "passive"))
      (node (ref "R46") (pin "2") (pinfunction "2_2") (pintype "passive"))
    )
    (net (code "61") (name "Net-(R47-Pad1)") (class "Default")
      (node (ref "R47") (pin "1") (pinfunction "1_1") (pintype "passive"))
      (node (ref "R48") (pin "2") (pinfunction "2_2") (pintype "passive"))
    )
    (net (code "62") (name "Net-(R49-Pad1)") (class "Default")
      (node (ref "R49") (pin "1") (pinfunction "1_1") (pintype "passive"))
      (node (ref "R50") (pin "2") (pinfunction "2_2") (pintype "passive"))
    )
    (net (code "63") (name "Net-(R51-Pad1)") (class "Default")
      (node (ref "R51") (pin "1") (pinfunction "1_1") (pintype "passive"))
      (node (ref "R52") (pin "2") (pinfunction "2_2") (pintype "passive"))
    )
    (net (code "64") (name "Net-(R53-Pad1)") (class "Default")
      (node (ref "R53") (pin "1") (pinfunction "1_1") (pintype "passive"))
      (node (ref "U$1") (pin "B") (pinfunction "B_B") (pintype "passive"))
    )
    (net (code "65") (name "unconnected-(U$1-PadC2)") (class "Default")
      (node (ref "U$1") (pin "C2") (pinfunction "C2_C2") (pintype "passive"))
    )
  )
)
